# Sheet3.net
KiCad netlist of a schematic drawn in Altium Designer
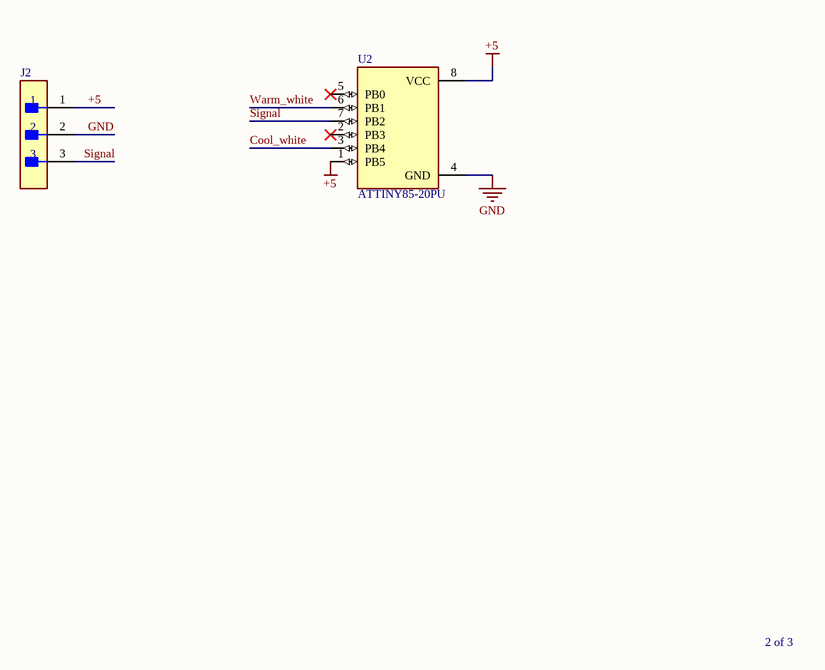
[diagram p0: Sheet3.SchDoc]

(export (version "E")
  (design (tool "Eeschema 10.0.6"))
  (components
    (comp (ref "J2")
      (value "B3B-XH-A(LF)(SN)")
      (footprint "FP-B3B-XH-A_LF_SN-MFG")
      (description "CONN HEADER VERT 3POS 2.5MM")
      (libsource (lib "Altium Content Vault") (part "0d3f023dd272f625e17a2be33dea85f"))
    )
    (comp (ref "U2")
      (value "ATTINY85-20PU")
      (footprint "DIP762W46P254L927H533Q8B")
      (fields (field (name "MF") "Microchip"))
      (libsource (lib "ATTINY85-20PU") (part "ATTINY85-20PU"))
    )
  )
  (nets
    (net (code "1") (name "+5") (class "Default")
      (node (ref "J2") (pin "1") (pinfunction "1_1") (pintype "passive"))
      (node (ref "U2") (pin "1") (pinfunction "PB5_1") (pintype "bidirectional"))
      (node (ref "U2") (pin "8") (pinfunction "VCC_8") (pintype "power_in"))
    )
    (net (code "2") (name "/Cool_white") (class "Default")
      (node (ref "U2") (pin "3") (pinfunction "PB4_3") (pintype "bidirectional"))
    )
    (net (code "3") (name "/Signal") (class "Default")
      (node (ref "J2") (pin "3") (pinfunction "3_3") (pintype "passive"))
      (node (ref "U2") (pin "7") (pinfunction "PB2_7") (pintype "bidirectional"))
    )
    (net (code "4") (name "/Warm_white") (class "Default")
      (node (ref "U2") (pin "6") (pinfunction "PB1_6") (pintype "bidirectional"))
    )
    (net (code "5") (name "GND") (class "Default")
      (node (ref "J2") (pin "2") (pinfunction "2_2") (pintype "passive"))
      (node (ref "U2") (pin "4") (pinfunction "GND_4") (pintype "power_in"))
    )
    (net (code "6") (name "unconnected-(U2-PB0-Pad5)") (class "Default")
      (node (ref "U2") (pin "5") (pinfunction "PB0_5") (pintype "bidirectional+no_connect"))
    )
    (net (code "7") (name "unconnected-(U2-PB3-Pad2)") (class "Default")
      (node (ref "U2") (pin "2") (pinfunction "PB3_2") (pintype "bidirectional+no_connect"))
    )
  )
)
